# LTM4625.net
KiCad netlist of a schematic drawn in Altium Designer
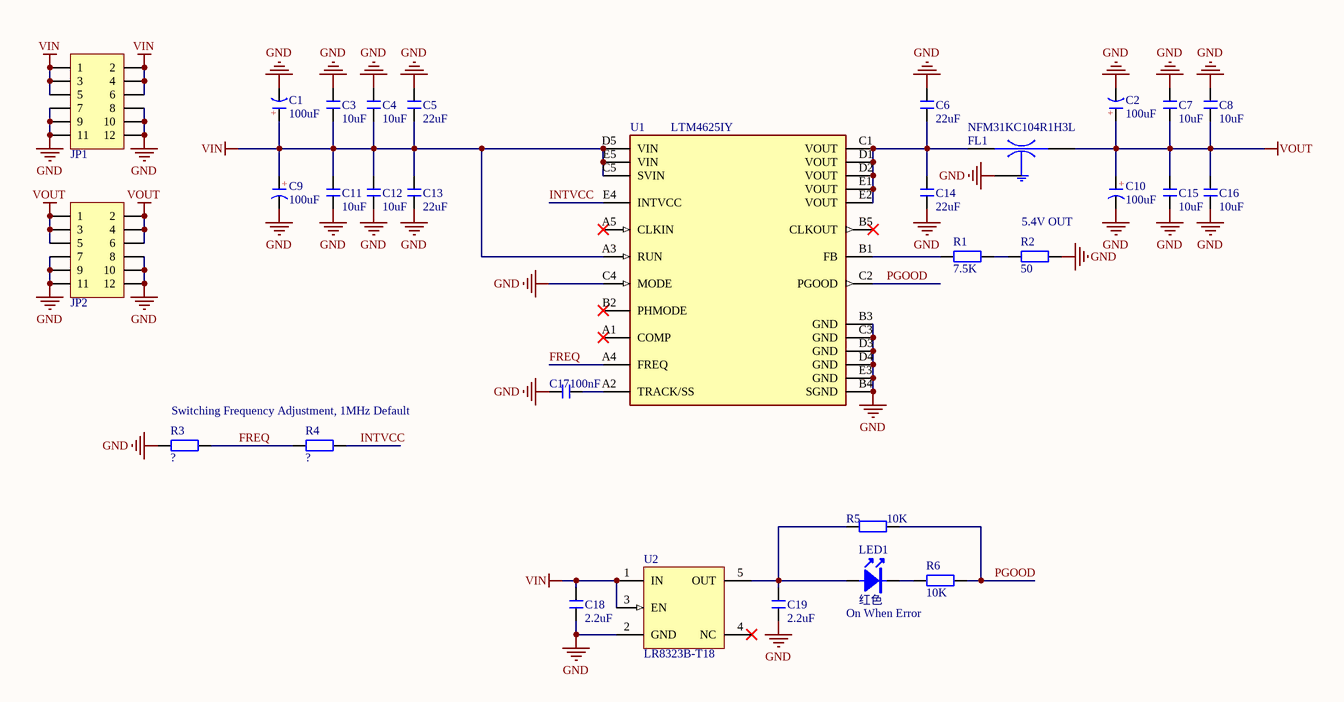
[diagram p0: LTM4625.SchDoc]

(export (version "E")
  (design (tool "Eeschema 10.0.6"))
  (components
    (comp (ref "C1")
      (value "100uF")
      (footprint "CAP 2.5*6.3*7")
      (description "直插电解电容")
      (libsource (lib "01 - 电容-电阻-电感") (part "CE"))
    )
    (comp (ref "C2")
      (value "100uF")
      (footprint "CAP 2.5*6.3*7")
      (description "直插电解电容")
      (libsource (lib "01 - 电容-电阻-电感") (part "CE"))
    )
    (comp (ref "C3")
      (value "10uF")
      (footprint "C 1210_L")
      (description "贴片电容")
      (libsource (lib "01 - 电容-电阻-电感") (part "C"))
    )
    (comp (ref "C4")
      (value "10uF")
      (footprint "C 1210_L")
      (description "贴片电容")
      (libsource (lib "01 - 电容-电阻-电感") (part "C"))
    )
    (comp (ref "C5")
      (value "22uF")
      (footprint "C 1206_L")
      (description "贴片电容")
      (libsource (lib "01 - 电容-电阻-电感") (part "C"))
    )
    (comp (ref "C6")
      (value "22uF")
      (footprint "C 1206_L")
      (description "贴片电容")
      (libsource (lib "01 - 电容-电阻-电感") (part "C"))
    )
    (comp (ref "C7")
      (value "10uF")
      (footprint "C 1210_L")
      (description "贴片电容")
      (libsource (lib "01 - 电容-电阻-电感") (part "C"))
    )
    (comp (ref "C8")
      (value "10uF")
      (footprint "C 1210_L")
      (description "贴片电容")
      (libsource (lib "01 - 电容-电阻-电感") (part "C"))
    )
    (comp (ref "C9")
      (value "100uF")
      (footprint "CAP 2.5*6.3*7")
      (description "直插电解电容")
      (libsource (lib "01 - 电容-电阻-电感") (part "CE"))
    )
    (comp (ref "C10")
      (value "100uF")
      (footprint "CAP 2.5*6.3*7")
      (description "直插电解电容")
      (libsource (lib "01 - 电容-电阻-电感") (part "CE"))
    )
    (comp (ref "C11")
      (value "10uF")
      (footprint "C 1210_L")
      (description "贴片电容")
      (libsource (lib "01 - 电容-电阻-电感") (part "C"))
    )
    (comp (ref "C12")
      (value "10uF")
      (footprint "C 1210_L")
      (description "贴片电容")
      (libsource (lib "01 - 电容-电阻-电感") (part "C"))
    )
    (comp (ref "C13")
      (value "22uF")
      (footprint "C 1206_L")
      (description "贴片电容")
      (libsource (lib "01 - 电容-电阻-电感") (part "C"))
    )
    (comp (ref "C14")
      (value "22uF")
      (footprint "C 1206_L")
      (description "贴片电容")
      (libsource (lib "01 - 电容-电阻-电感") (part "C"))
    )
    (comp (ref "C15")
      (value "10uF")
      (footprint "C 1210_L")
      (description "贴片电容")
      (libsource (lib "01 - 电容-电阻-电感") (part "C"))
    )
    (comp (ref "C16")
      (value "10uF")
      (footprint "C 1210_L")
      (description "贴片电容")
      (libsource (lib "01 - 电容-电阻-电感") (part "C"))
    )
    (comp (ref "C17")
      (value "100nF")
      (footprint "C 0603_L")
      (description "贴片电容")
      (libsource (lib "01 - 电容-电阻-电感") (part "C"))
    )
    (comp (ref "C18")
      (value "2.2uF")
      (footprint "C 0603_L")
      (description "贴片电容")
      (libsource (lib "01 - 电容-电阻-电感") (part "C"))
    )
    (comp (ref "C19")
      (value "2.2uF")
      (footprint "C 0603_L")
      (description "贴片电容")
      (libsource (lib "01 - 电容-电阻-电感") (part "C"))
    )
    (comp (ref "FL1")
      (value "NFM31KC104R1H3L")
      (footprint "FIL_NFM31KC104R1H3L")
      (description "SMD Capacitor with Capacitance: 0.10uF Tol. 20%. Rated Voltage: 50Vdc")
      (fields (field (name "MF") "Murata"))
      (libsource (lib "NFM31KC104R1H3L") (part "NFM31KC104R1H3L"))
    )
    (comp (ref "JP1")
      (value "Header 6X2")
      (footprint "HDR2.54-LI-2x6P")
      (description "6*2P接插件")
      (libsource (lib "18 - 接插件-脚距2.54mm (100mil) ") (part "Header  6X2"))
    )
    (comp (ref "JP2")
      (value "Header 6X2")
      (footprint "HDR2.54-LI-2x6P")
      (description "6*2P接插件")
      (libsource (lib "18 - 接插件-脚距2.54mm (100mil) ") (part "Header  6X2"))
    )
    (comp (ref "LED1")
      (value "红色")
      (footprint "LED 0603R")
      (description "贴片LED")
      (libsource (lib "02 - 二极管(LED)-三极管-整流桥") (part "LED-SMD"))
    )
    (comp (ref "R1")
      (value "7.5K")
      (footprint "R 0603_L")
      (description "贴片电阻")
      (libsource (lib "01 - 电容-电阻-电感") (part "R"))
    )
    (comp (ref "R2")
      (value "50")
      (footprint "R 0603_L")
      (description "贴片电阻")
      (libsource (lib "01 - 电容-电阻-电感") (part "R"))
    )
    (comp (ref "R3")
      (value "?")
      (footprint "R 0603_L")
      (description "贴片电阻")
      (libsource (lib "01 - 电容-电阻-电感") (part "R"))
    )
    (comp (ref "R4")
      (value "?")
      (footprint "R 0603_L")
      (description "贴片电阻")
      (libsource (lib "01 - 电容-电阻-电感") (part "R"))
    )
    (comp (ref "R5")
      (value "10K")
      (footprint "R 0603_L")
      (description "贴片电阻")
      (libsource (lib "01 - 电容-电阻-电感") (part "R"))
    )
    (comp (ref "R6")
      (value "10K")
      (footprint "R 0603_L")
      (description "贴片电阻")
      (libsource (lib "01 - 电容-电阻-电感") (part "R"))
    )
    (comp (ref "U1")
      (value "LTM4625IY")
      (footprint "FP-BGA-25-05-08-1905-MFG")
      (description "DC DC CONVERTER 0.6-5.5V")
      (libsource (lib "LTM4625IY") (part "LTM4625IY"))
    )
    (comp (ref "U2")
      (value "LR8323B-T18")
      (footprint "DBV0005A_L")
      (description "None")
      (libsource (lib "LR8323B-T18") (part "LR8323B-T18"))
    )
  )
  (nets
    (net (code "1") (name "/FREQ") (class "Default")
      (node (ref "R3") (pin "2") (pinfunction "2_2") (pintype "passive"))
      (node (ref "R4") (pin "1") (pinfunction "1_1") (pintype "passive"))
      (node (ref "U1") (pin "A4") (pinfunction "FREQ_A4") (pintype "passive"))
    )
    (net (code "2") (name "/INTVCC") (class "Default")
      (node (ref "R4") (pin "2") (pinfunction "2_2") (pintype "passive"))
      (node (ref "U1") (pin "E4") (pinfunction "INTVCC_E4") (pintype "power_in"))
    )
    (net (code "3") (name "/PGOOD") (class "Default")
      (node (ref "R5") (pin "1") (pinfunction "1_1") (pintype "passive"))
      (node (ref "R6") (pin "2") (pinfunction "2_2") (pintype "passive"))
      (node (ref "U1") (pin "C2") (pinfunction "PGOOD_C2") (pintype "output"))
    )
    (net (code "4") (name "GND") (class "Default")
      (node (ref "C1") (pin "2") (pinfunction "K_2") (pintype "passive"))
      (node (ref "C10") (pin "2") (pinfunction "K_2") (pintype "passive"))
      (node (ref "C11") (pin "2") (pinfunction "2_2") (pintype "passive"))
      (node (ref "C12") (pin "2") (pinfunction "2_2") (pintype "passive"))
      (node (ref "C13") (pin "2") (pinfunction "2_2") (pintype "passive"))
      (node (ref "C14") (pin "2") (pinfunction "2_2") (pintype "passive"))
      (node (ref "C15") (pin "2") (pinfunction "2_2") (pintype "passive"))
      (node (ref "C16") (pin "2") (pinfunction "2_2") (pintype "passive"))
      (node (ref "C17") (pin "1") (pinfunction "1_1") (pintype "passive"))
      (node (ref "C18") (pin "1") (pinfunction "1_1") (pintype "passive"))
      (node (ref "C19") (pin "1") (pinfunction "1_1") (pintype "passive"))
      (node (ref "C2") (pin "2") (pinfunction "K_2") (pintype "passive"))
      (node (ref "C3") (pin "2") (pinfunction "2_2") (pintype "passive"))
      (node (ref "C4") (pin "2") (pinfunction "2_2") (pintype "passive"))
      (node (ref "C5") (pin "2") (pinfunction "2_2") (pintype "passive"))
      (node (ref "C6") (pin "2") (pinfunction "2_2") (pintype "passive"))
      (node (ref "C7") (pin "2") (pinfunction "2_2") (pintype "passive"))
      (node (ref "C8") (pin "2") (pinfunction "2_2") (pintype "passive"))
      (node (ref "C9") (pin "2") (pinfunction "K_2") (pintype "passive"))
      (node (ref "FL1") (pin "2") (pinfunction "GND_2") (pintype "power_in"))
      (node (ref "JP1") (pin "10") (pinfunction "10_10") (pintype "passive"))
      (node (ref "JP1") (pin "11") (pinfunction "11_11") (pintype "passive"))
      (node (ref "JP1") (pin "12") (pinfunction "12_12") (pintype "passive"))
      (node (ref "JP1") (pin "7") (pinfunction "7_7") (pintype "passive"))
      (node (ref "JP1") (pin "8") (pinfunction "8_8") (pintype "passive"))
      (node (ref "JP1") (pin "9") (pinfunction "9_9") (pintype "passive"))
      (node (ref "JP2") (pin "10") (pinfunction "10_10") (pintype "passive"))
      (node (ref "JP2") (pin "11") (pinfunction "11_11") (pintype "passive"))
      (node (ref "JP2") (pin "12") (pinfunction "12_12") (pintype "passive"))
      (node (ref "JP2") (pin "7") (pinfunction "7_7") (pintype "passive"))
      (node (ref "JP2") (pin "8") (pinfunction "8_8") (pintype "passive"))
      (node (ref "JP2") (pin "9") (pinfunction "9_9") (pintype "passive"))
      (node (ref "R2") (pin "2") (pinfunction "2_2") (pintype "passive"))
      (node (ref "R3") (pin "1") (pinfunction "1_1") (pintype "passive"))
      (node (ref "U1") (pin "B3") (pinfunction "GND_B3") (pintype "power_in"))
      (node (ref "U1") (pin "B4") (pinfunction "SGND_B4") (pintype "power_in"))
      (node (ref "U1") (pin "C3") (pinfunction "GND_C3") (pintype "power_in"))
      (node (ref "U1") (pin "C4") (pinfunction "MODE_C4") (pintype "input"))
      (node (ref "U1") (pin "D3") (pinfunction "GND_D3") (pintype "power_in"))
      (node (ref "U1") (pin "D4") (pinfunction "GND_D4") (pintype "power_in"))
      (node (ref "U1") (pin "E3") (pinfunction "GND_E3") (pintype "power_in"))
      (node (ref "U2") (pin "2") (pinfunction "GND_2") (pintype "power_in"))
    )
    (net (code "5") (name "Net-(FL1-IN)") (class "Default")
      (node (ref "C14") (pin "1") (pinfunction "1_1") (pintype "passive"))
      (node (ref "C6") (pin "1") (pinfunction "1_1") (pintype "passive"))
      (node (ref "FL1") (pin "1") (pinfunction "IN_1") (pintype "passive"))
      (node (ref "U1") (pin "C1") (pinfunction "VOUT_C1") (pintype "power_in"))
      (node (ref "U1") (pin "D1") (pinfunction "VOUT_D1") (pintype "power_in"))
      (node (ref "U1") (pin "D2") (pinfunction "VOUT_D2") (pintype "power_in"))
      (node (ref "U1") (pin "E1") (pinfunction "VOUT_E1") (pintype "power_in"))
      (node (ref "U1") (pin "E2") (pinfunction "VOUT_E2") (pintype "power_in"))
    )
    (net (code "6") (name "Net-(LED1-A)") (class "Default")
      (node (ref "C19") (pin "2") (pinfunction "2_2") (pintype "passive"))
      (node (ref "LED1") (pin "1") (pinfunction "A_1") (pintype "passive"))
      (node (ref "R5") (pin "2") (pinfunction "2_2") (pintype "passive"))
      (node (ref "U2") (pin "5") (pinfunction "OUT_5") (pintype "power_in"))
    )
    (net (code "7") (name "Net-(LED1-K)") (class "Default")
      (node (ref "LED1") (pin "2") (pinfunction "K_2") (pintype "passive"))
      (node (ref "R6") (pin "1") (pinfunction "1_1") (pintype "passive"))
    )
    (net (code "8") (name "Net-(R1-Pad2)") (class "Default")
      (node (ref "R1") (pin "2") (pinfunction "2_2") (pintype "passive"))
      (node (ref "R2") (pin "1") (pinfunction "1_1") (pintype "passive"))
    )
    (net (code "9") (name "Net-(U1-FB)") (class "Default")
      (node (ref "R1") (pin "1") (pinfunction "1_1") (pintype "passive"))
      (node (ref "U1") (pin "B1") (pinfunction "FB_B1") (pintype "passive"))
    )
    (net (code "10") (name "Net-(U1-TRACK{slash}SS)") (class "Default")
      (node (ref "C17") (pin "2") (pinfunction "2_2") (pintype "passive"))
      (node (ref "U1") (pin "A2") (pinfunction "TRACK/SS_A2") (pintype "passive"))
    )
    (net (code "11") (name "VIN") (class "Default")
      (node (ref "C1") (pin "1") (pinfunction "A_1") (pintype "passive"))
      (node (ref "C11") (pin "1") (pinfunction "1_1") (pintype "passive"))
      (node (ref "C12") (pin "1") (pinfunction "1_1") (pintype "passive"))
      (node (ref "C13") (pin "1") (pinfunction "1_1") (pintype "passive"))
      (node (ref "C18") (pin "2") (pinfunction "2_2") (pintype "passive"))
      (node (ref "C3") (pin "1") (pinfunction "1_1") (pintype "passive"))
      (node (ref "C4") (pin "1") (pinfunction "1_1") (pintype "passive"))
      (node (ref "C5") (pin "1") (pinfunction "1_1") (pintype "passive"))
      (node (ref "C9") (pin "1") (pinfunction "A_1") (pintype "passive"))
      (node (ref "JP1") (pin "1") (pinfunction "1_1") (pintype "passive"))
      (node (ref "JP1") (pin "2") (pinfunction "2_2") (pintype "passive"))
      (node (ref "JP1") (pin "3") (pinfunction "3_3") (pintype "passive"))
      (node (ref "JP1") (pin "4") (pinfunction "4_4") (pintype "passive"))
      (node (ref "JP1") (pin "5") (pinfunction "5_5") (pintype "passive"))
      (node (ref "JP1") (pin "6") (pinfunction "6_6") (pintype "passive"))
      (node (ref "U1") (pin "A3") (pinfunction "RUN_A3") (pintype "input"))
      (node (ref "U1") (pin "C5") (pinfunction "SVIN_C5") (pintype "power_in"))
      (node (ref "U1") (pin "D5") (pinfunction "VIN_D5") (pintype "power_in"))
      (node (ref "U1") (pin "E5") (pinfunction "VIN_E5") (pintype "power_in"))
      (node (ref "U2") (pin "1") (pinfunction "IN_1") (pintype "power_in"))
      (node (ref "U2") (pin "3") (pinfunction "EN_3") (pintype "input"))
    )
    (net (code "12") (name "VOUT") (class "Default")
      (node (ref "C10") (pin "1") (pinfunction "A_1") (pintype "passive"))
      (node (ref "C15") (pin "1") (pinfunction "1_1") (pintype "passive"))
      (node (ref "C16") (pin "1") (pinfunction "1_1") (pintype "passive"))
      (node (ref "C2") (pin "1") (pinfunction "A_1") (pintype "passive"))
      (node (ref "C7") (pin "1") (pinfunction "1_1") (pintype "passive"))
      (node (ref "C8") (pin "1") (pinfunction "1_1") (pintype "passive"))
      (node (ref "FL1") (pin "3") (pinfunction "OUT_3") (pintype "passive"))
      (node (ref "JP2") (pin "1") (pinfunction "1_1") (pintype "passive"))
      (node (ref "JP2") (pin "2") (pinfunction "2_2") (pintype "passive"))
      (node (ref "JP2") (pin "3") (pinfunction "3_3") (pintype "passive"))
      (node (ref "JP2") (pin "4") (pinfunction "4_4") (pintype "passive"))
      (node (ref "JP2") (pin "5") (pinfunction "5_5") (pintype "passive"))
      (node (ref "JP2") (pin "6") (pinfunction "6_6") (pintype "passive"))
    )
    (net (code "13") (name "unconnected-(U1-CLKIN-PadA5)") (class "Default")
      (node (ref "U1") (pin "A5") (pinfunction "CLKIN_A5") (pintype "input+no_connect"))
    )
    (net (code "14") (name "unconnected-(U1-CLKOUT-PadB5)") (class "Default")
      (node (ref "U1") (pin "B5") (pinfunction "CLKOUT_B5") (pintype "output+no_connect"))
    )
    (net (code "15") (name "unconnected-(U1-COMP-PadA1)") (class "Default")
      (node (ref "U1") (pin "A1") (pinfunction "COMP_A1") (pintype "passive+no_connect"))
    )
    (net (code "16") (name "unconnected-(U1-PHMODE-PadB2)") (class "Default")
      (node (ref "U1") (pin "B2") (pinfunction "PHMODE_B2") (pintype "passive+no_connect"))
    )
    (net (code "17") (name "unconnected-(U2-NC-Pad4)") (class "Default")
      (node (ref "U2") (pin "4") (pinfunction "NC_4") (pintype "passive+no_connect"))
    )
  )
)
